# power_amp.net
KiCad netlist of a schematic drawn in Altium Designer
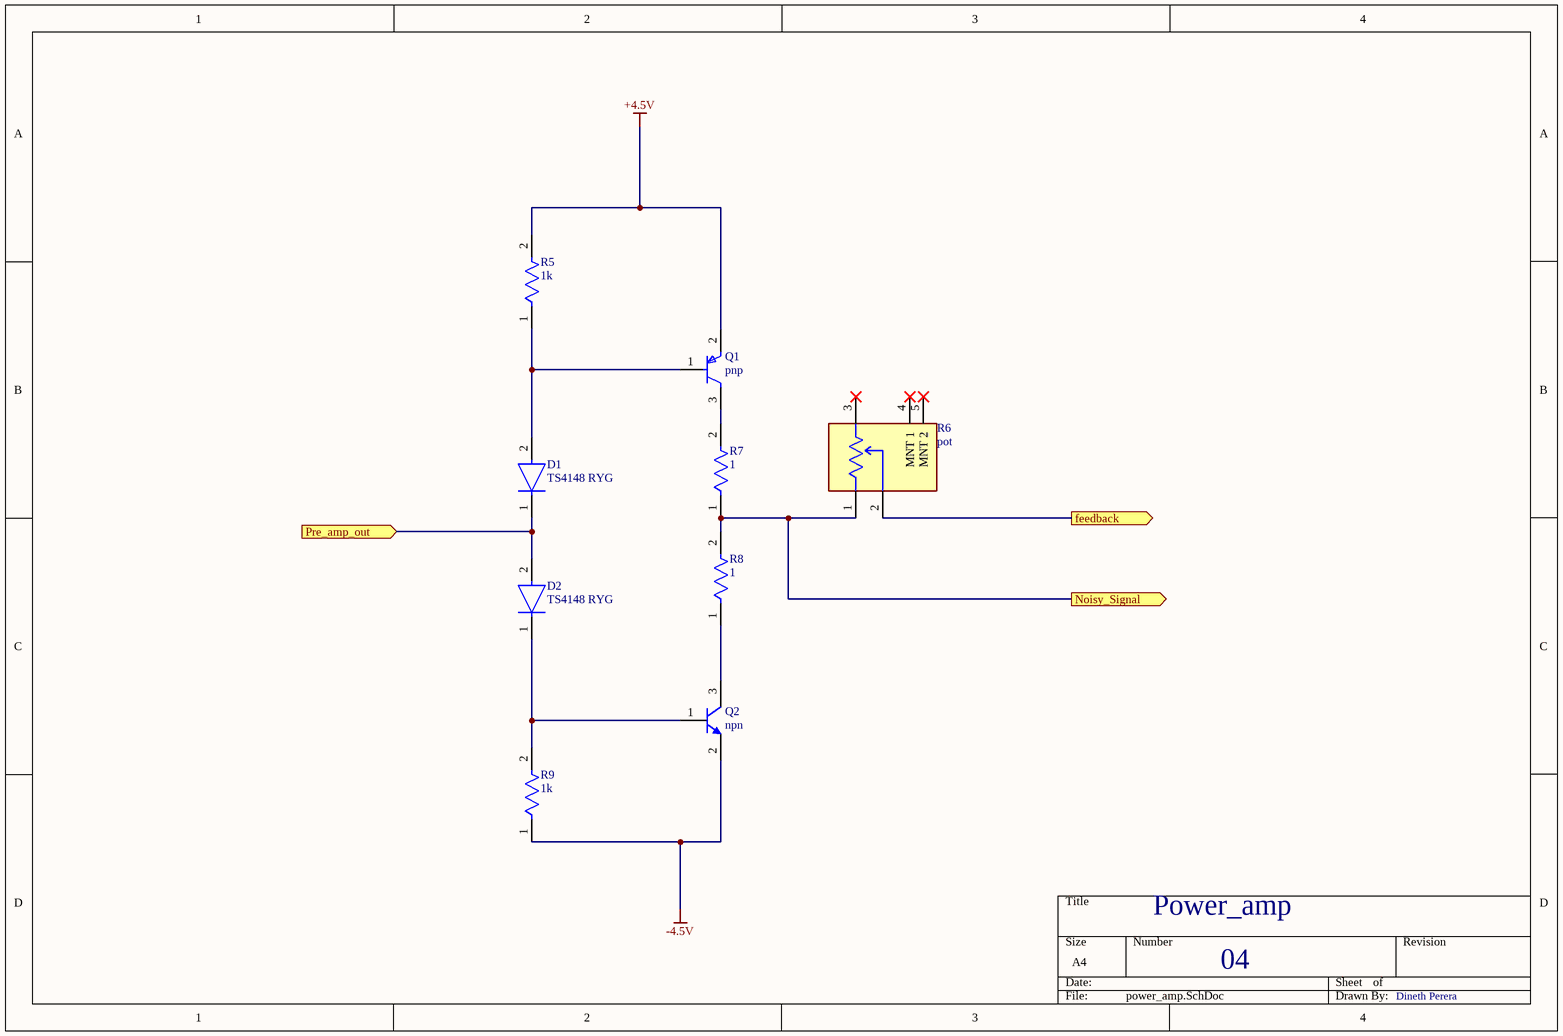
[diagram p0: power_amp.SchDoc]

(export (version "E")
  (design (tool "Eeschema 10.0.6"))
  (components
    (comp (ref "D1")
      (value "TS4148 RYG")
      (footprint "FP-TS4148_RYG-MFG")
      (description "Rectifier Diode Switching 75V 0.15A 4ns 2-Pin Case 0805(2012Metric) T/R")
      (libsource (lib "Altium Content Vault") (part "d7152d700b627762746794eb795d46e"))
    )
    (comp (ref "D2")
      (value "TS4148 RYG")
      (footprint "FP-TS4148_RYG-MFG")
      (description "Rectifier Diode Switching 75V 0.15A 4ns 2-Pin Case 0805(2012Metric) T/R")
      (libsource (lib "Altium Content Vault") (part "d7152d700b627762746794eb795d46e"))
    )
    (comp (ref "Q1")
      (value "pnp")
      (footprint "FP-318BM-MFG")
      (description "MMBTA56 Small Signal Bipolar Transistor, 0.5A I(C), 80V V(BR)CEO, 1-Element, PNP, Silicon")
      (libsource (lib "Altium Content Vault") (part "0e8486ed3b47d9c69b8404ba87cf0f7"))
    )
    (comp (ref "Q2")
      (value "npn")
      (footprint "INF-SOT23_L")
      (description "NPN Silicon AF Transistor, 80 V VCEO, 500 mA IC, SOT23, Reel, Green")
      (fields (field (name "PARTNUMBER") "SMBTA06") (field (name "MANUFACTURER") "Infineon"))
      (libsource (lib "Altium Content Vault") (part "INF-BJTNPN-BEC-3"))
    )
    (comp (ref "R5")
      (value "1k")
      (footprint "FP-ERA6A-IPC_C")
      (description "RES 1K OHM 0.1% 1/8W 0805")
      (fields (field (name "TOLERANCE") "0.1%"))
      (libsource (lib "Altium Content Vault") (part "1029c3af85768c4190bb7ad29bc67b5"))
    )
    (comp (ref "R6")
      (value "pot")
      (footprint "FP-PTV09A-4-MFG")
      (description "Res Carbon Film POT 10K Ohm 20% 1/20W 1(Elec)/1(Mech)Turn 6mm Pin Bracket Mount/Through Hole")
      (fields (field (name "MANUFACTURER PART NUMBER") "PTV09A-4020U-B103"))
      (libsource (lib "Altium Content Vault") (part "3454c451b146ec4d4239c7813666f62"))
    )
    (comp (ref "R7")
      (value "1")
      (footprint "FP-CRCW0805-e3-MFG")
      (description "RES Thick Film, 1Ω, 1%, 0.125W, 100ppm/°C, 0805")
      (fields (field (name "TOLERANCE") "1%"))
      (libsource (lib "Altium Content Vault") (part "1029c3af85768c4190bb7ad29bc67b5"))
    )
    (comp (ref "R8")
      (value "1")
      (footprint "FP-CRCW0805-e3-MFG")
      (description "RES Thick Film, 1Ω, 1%, 0.125W, 100ppm/°C, 0805")
      (fields (field (name "TOLERANCE") "1%"))
      (libsource (lib "Altium Content Vault") (part "1029c3af85768c4190bb7ad29bc67b5"))
    )
    (comp (ref "R9")
      (value "1k")
      (footprint "FP-ERA6A-IPC_C")
      (description "RES 1K OHM 0.1% 1/8W 0805")
      (fields (field (name "TOLERANCE") "0.1%"))
      (libsource (lib "Altium Content Vault") (part "1029c3af85768c4190bb7ad29bc67b5"))
    )
  )
  (nets
    (net (code "1") (name "+4.5V") (class "Default")
      (node (ref "Q1") (pin "2") (pinfunction "E_2") (pintype "passive"))
      (node (ref "R5") (pin "2") (pinfunction "2_2") (pintype "passive"))
    )
    (net (code "2") (name "-4.5V") (class "Default")
      (node (ref "Q2") (pin "2") (pinfunction "E_2") (pintype "passive"))
      (node (ref "R9") (pin "1") (pinfunction "1_1") (pintype "passive"))
    )
    (net (code "3") (name "/Noisy_Signal") (class "Default")
      (node (ref "R6") (pin "1") (pinfunction "1_1") (pintype "passive"))
      (node (ref "R7") (pin "1") (pinfunction "1_1") (pintype "passive"))
      (node (ref "R8") (pin "2") (pinfunction "2_2") (pintype "passive"))
    )
    (net (code "4") (name "/Pre_amp_out") (class "Default")
      (node (ref "D1") (pin "1") (pinfunction "C_1") (pintype "passive"))
      (node (ref "D2") (pin "2") (pinfunction "A_2") (pintype "passive"))
    )
    (net (code "5") (name "/feedback") (class "Default")
      (node (ref "R6") (pin "2") (pinfunction "2_2") (pintype "passive"))
    )
    (net (code "6") (name "Net-(D1-A)") (class "Default")
      (node (ref "D1") (pin "2") (pinfunction "A_2") (pintype "passive"))
      (node (ref "Q1") (pin "1") (pinfunction "B_1") (pintype "passive"))
      (node (ref "R5") (pin "1") (pinfunction "1_1") (pintype "passive"))
    )
    (net (code "7") (name "Net-(D2-C)") (class "Default")
      (node (ref "D2") (pin "1") (pinfunction "C_1") (pintype "passive"))
      (node (ref "Q2") (pin "1") (pinfunction "B_1") (pintype "passive"))
      (node (ref "R9") (pin "2") (pinfunction "2_2") (pintype "passive"))
    )
    (net (code "8") (name "Net-(Q1-C)") (class "Default")
      (node (ref "Q1") (pin "3") (pinfunction "C_3") (pintype "passive"))
      (node (ref "R7") (pin "2") (pinfunction "2_2") (pintype "passive"))
    )
    (net (code "9") (name "Net-(Q2-C)") (class "Default")
      (node (ref "Q2") (pin "3") (pinfunction "C_3") (pintype "passive"))
      (node (ref "R8") (pin "1") (pinfunction "1_1") (pintype "passive"))
    )
    (net (code "10") (name "unconnected-(R6-MNT_1-Pad4)") (class "Default")
      (node (ref "R6") (pin "4") (pinfunction "MNT_1_4") (pintype "passive+no_connect"))
    )
    (net (code "11") (name "unconnected-(R6-MNT_2-Pad5)") (class "Default")
      (node (ref "R6") (pin "5") (pinfunction "MNT_2_5") (pintype "passive+no_connect"))
    )
    (net (code "12") (name "unconnected-(R6-Pad3)") (class "Default")
      (node (ref "R6") (pin "3") (pinfunction "3_3") (pintype "passive+no_connect"))
    )
  )
)
